# PCB_1_1.net
KiCad netlist of a schematic drawn in EAGLE
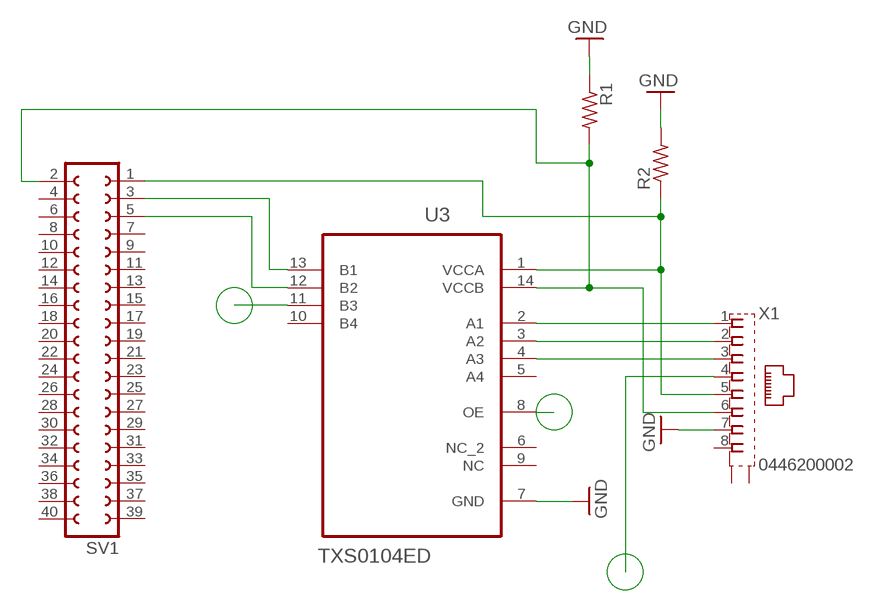
[diagram p0: schematic, sheet 1]

(export (version "E")
  (design (tool "Eeschema 10.0.6"))
  (components
    (comp (ref "R1")
      (value "R-US_R0805")
      (footprint "eagle-import:R0805")
      (libsource (lib "eagle-import") (part "R-US_R0805"))
    )
    (comp (ref "R2")
      (value "R-US_R0805")
      (footprint "eagle-import:R0805")
      (libsource (lib "eagle-import") (part "R-US_R0805"))
    )
    (comp (ref "SV1")
      (value "FE20-2")
      (footprint "eagle-import:FE20-2")
      (libsource (lib "eagle-import") (part "FE20-2"))
    )
    (comp (ref "U3")
      (value "TXS0104ED")
      (footprint "eagle-import:SOIC127P600X175-14N")
      (fields (field (name "MF") "Texas Instruments"))
      (libsource (lib "eagle-import") (part "TXS0104ED"))
    )
    (comp (ref "X1")
      (value "0446200002")
      (footprint "eagle-import:0446200002")
      (fields (field (name "MF") "Molex, LLC"))
      (libsource (lib "eagle-import") (part "0446200002"))
    )
  )
  (nets
    (net (code "1") (name "GND") (class "Default")
      (node (ref "R1") (pin "1") (pinfunction "1_1") (pintype "passive"))
      (node (ref "R2") (pin "2") (pinfunction "2_2") (pintype "passive"))
      (node (ref "U3") (pin "7") (pinfunction "GND_7") (pintype "passive"))
      (node (ref "X1") (pin "7") (pinfunction "7_7") (pintype "passive"))
    )
    (net (code "2") (name "Net-(U3-A1)") (class "Default")
      (node (ref "U3") (pin "2") (pinfunction "A1_2") (pintype "input"))
      (node (ref "X1") (pin "1") (pinfunction "1_1") (pintype "passive"))
    )
    (net (code "3") (name "Net-(U3-A2)") (class "Default")
      (node (ref "U3") (pin "3") (pinfunction "A2_3") (pintype "input"))
      (node (ref "X1") (pin "2") (pinfunction "2_2") (pintype "passive"))
    )
    (net (code "4") (name "Net-(U3-A3)") (class "Default")
      (node (ref "U3") (pin "4") (pinfunction "A3_4") (pintype "input"))
      (node (ref "X1") (pin "3") (pinfunction "3_3") (pintype "passive"))
    )
    (net (code "5") (name "Net-(U3-B1)") (class "Default")
      (node (ref "SV1") (pin "3") (pinfunction "3_3") (pintype "passive"))
      (node (ref "U3") (pin "13") (pinfunction "B1_13") (pintype "output"))
    )
    (net (code "6") (name "Net-(U3-B2)") (class "Default")
      (node (ref "SV1") (pin "5") (pinfunction "5_5") (pintype "passive"))
      (node (ref "U3") (pin "12") (pinfunction "B2_12") (pintype "output"))
    )
    (net (code "7") (name "Net-(U3-VCCA)") (class "Default")
      (node (ref "R2") (pin "1") (pinfunction "1_1") (pintype "passive"))
      (node (ref "SV1") (pin "1") (pinfunction "1_1") (pintype "passive"))
      (node (ref "U3") (pin "1") (pinfunction "VCCA_1") (pintype "power_in"))
      (node (ref "X1") (pin "5") (pinfunction "5_5") (pintype "passive"))
    )
    (net (code "8") (name "Net-(U3-VCCB)") (class "Default")
      (node (ref "R1") (pin "2") (pinfunction "2_2") (pintype "passive"))
      (node (ref "SV1") (pin "2") (pinfunction "2_2") (pintype "passive"))
      (node (ref "U3") (pin "14") (pinfunction "VCCB_14") (pintype "power_in"))
      (node (ref "X1") (pin "6") (pinfunction "6_6") (pintype "passive"))
    )
    (net (code "9") (name "unconnected-(SV1-Pad4)") (class "Default")
      (node (ref "SV1") (pin "4") (pinfunction "4_4") (pintype "passive"))
    )
    (net (code "10") (name "unconnected-(SV1-Pad6)") (class "Default")
      (node (ref "SV1") (pin "6") (pinfunction "6_6") (pintype "passive"))
    )
    (net (code "11") (name "unconnected-(SV1-Pad7)") (class "Default")
      (node (ref "SV1") (pin "7") (pinfunction "7_7") (pintype "passive"))
    )
    (net (code "12") (name "unconnected-(SV1-Pad8)") (class "Default")
      (node (ref "SV1") (pin "8") (pinfunction "8_8") (pintype "passive"))
    )
    (net (code "13") (name "unconnected-(SV1-Pad9)") (class "Default")
      (node (ref "SV1") (pin "9") (pinfunction "9_9") (pintype "passive"))
    )
    (net (code "14") (name "unconnected-(SV1-Pad10)") (class "Default")
      (node (ref "SV1") (pin "10") (pinfunction "10_10") (pintype "passive"))
    )
    (net (code "15") (name "unconnected-(SV1-Pad11)") (class "Default")
      (node (ref "SV1") (pin "11") (pinfunction "11_11") (pintype "passive"))
    )
    (net (code "16") (name "unconnected-(SV1-Pad12)") (class "Default")
      (node (ref "SV1") (pin "12") (pinfunction "12_12") (pintype "passive"))
    )
    (net (code "17") (name "unconnected-(SV1-Pad13)") (class "Default")
      (node (ref "SV1") (pin "13") (pinfunction "13_13") (pintype "passive"))
    )
    (net (code "18") (name "unconnected-(SV1-Pad14)") (class "Default")
      (node (ref "SV1") (pin "14") (pinfunction "14_14") (pintype "passive"))
    )
    (net (code "19") (name "unconnected-(SV1-Pad15)") (class "Default")
      (node (ref "SV1") (pin "15") (pinfunction "15_15") (pintype "passive"))
    )
    (net (code "20") (name "unconnected-(SV1-Pad16)") (class "Default")
      (node (ref "SV1") (pin "16") (pinfunction "16_16") (pintype "passive"))
    )
    (net (code "21") (name "unconnected-(SV1-Pad17)") (class "Default")
      (node (ref "SV1") (pin "17") (pinfunction "17_17") (pintype "passive"))
    )
    (net (code "22") (name "unconnected-(SV1-Pad18)") (class "Default")
      (node (ref "SV1") (pin "18") (pinfunction "18_18") (pintype "passive"))
    )
    (net (code "23") (name "unconnected-(SV1-Pad19)") (class "Default")
      (node (ref "SV1") (pin "19") (pinfunction "19_19") (pintype "passive"))
    )
    (net (code "24") (name "unconnected-(SV1-Pad20)") (class "Default")
      (node (ref "SV1") (pin "20") (pinfunction "20_20") (pintype "passive"))
    )
    (net (code "25") (name "unconnected-(SV1-Pad21)") (class "Default")
      (node (ref "SV1") (pin "21") (pinfunction "21_21") (pintype "passive"))
    )
    (net (code "26") (name "unconnected-(SV1-Pad22)") (class "Default")
      (node (ref "SV1") (pin "22") (pinfunction "22_22") (pintype "passive"))
    )
    (net (code "27") (name "unconnected-(SV1-Pad23)") (class "Default")
      (node (ref "SV1") (pin "23") (pinfunction "23_23") (pintype "passive"))
    )
    (net (code "28") (name "unconnected-(SV1-Pad24)") (class "Default")
      (node (ref "SV1") (pin "24") (pinfunction "24_24") (pintype "passive"))
    )
    (net (code "29") (name "unconnected-(SV1-Pad25)") (class "Default")
      (node (ref "SV1") (pin "25") (pinfunction "25_25") (pintype "passive"))
    )
    (net (code "30") (name "unconnected-(SV1-Pad26)") (class "Default")
      (node (ref "SV1") (pin "26") (pinfunction "26_26") (pintype "passive"))
    )
    (net (code "31") (name "unconnected-(SV1-Pad27)") (class "Default")
      (node (ref "SV1") (pin "27") (pinfunction "27_27") (pintype "passive"))
    )
    (net (code "32") (name "unconnected-(SV1-Pad28)") (class "Default")
      (node (ref "SV1") (pin "28") (pinfunction "28_28") (pintype "passive"))
    )
    (net (code "33") (name "unconnected-(SV1-Pad29)") (class "Default")
      (node (ref "SV1") (pin "29") (pinfunction "29_29") (pintype "passive"))
    )
    (net (code "34") (name "unconnected-(SV1-Pad30)") (class "Default")
      (node (ref "SV1") (pin "30") (pinfunction "30_30") (pintype "passive"))
    )
    (net (code "35") (name "unconnected-(SV1-Pad31)") (class "Default")
      (node (ref "SV1") (pin "31") (pinfunction "31_31") (pintype "passive"))
    )
    (net (code "36") (name "unconnected-(SV1-Pad32)") (class "Default")
      (node (ref "SV1") (pin "32") (pinfunction "32_32") (pintype "passive"))
    )
    (net (code "37") (name "unconnected-(SV1-Pad33)") (class "Default")
      (node (ref "SV1") (pin "33") (pinfunction "33_33") (pintype "passive"))
    )
    (net (code "38") (name "unconnected-(SV1-Pad34)") (class "Default")
      (node (ref "SV1") (pin "34") (pinfunction "34_34") (pintype "passive"))
    )
    (net (code "39") (name "unconnected-(SV1-Pad35)") (class "Default")
      (node (ref "SV1") (pin "35") (pinfunction "35_35") (pintype "passive"))
    )
    (net (code "40") (name "unconnected-(SV1-Pad36)") (class "Default")
      (node (ref "SV1") (pin "36") (pinfunction "36_36") (pintype "passive"))
    )
    (net (code "41") (name "unconnected-(SV1-Pad37)") (class "Default")
      (node (ref "SV1") (pin "37") (pinfunction "37_37") (pintype "passive"))
    )
    (net (code "42") (name "unconnected-(SV1-Pad38)") (class "Default")
      (node (ref "SV1") (pin "38") (pinfunction "38_38") (pintype "passive"))
    )
    (net (code "43") (name "unconnected-(SV1-Pad39)") (class "Default")
      (node (ref "SV1") (pin "39") (pinfunction "39_39") (pintype "passive"))
    )
    (net (code "44") (name "unconnected-(SV1-Pad40)") (class "Default")
      (node (ref "SV1") (pin "40") (pinfunction "40_40") (pintype "passive"))
    )
    (net (code "45") (name "unconnected-(U3-A4-Pad5)") (class "Default")
      (node (ref "U3") (pin "5") (pinfunction "A4_5") (pintype "input"))
    )
    (net (code "46") (name "unconnected-(U3-B3-Pad11)") (class "Default")
      (node (ref "U3") (pin "11") (pinfunction "B3_11") (pintype "output"))
    )
    (net (code "47") (name "unconnected-(U3-B4-Pad10)") (class "Default")
      (node (ref "U3") (pin "10") (pinfunction "B4_10") (pintype "output"))
    )
    (net (code "48") (name "unconnected-(U3-NC-Pad9)") (class "Default")
      (node (ref "U3") (pin "9") (pinfunction "NC_9") (pintype "no_connect"))
    )
    (net (code "49") (name "unconnected-(U3-NC_2-Pad6)") (class "Default")
      (node (ref "U3") (pin "6") (pinfunction "NC_2_6") (pintype "no_connect"))
    )
    (net (code "50") (name "unconnected-(U3-OE-Pad8)") (class "Default")
      (node (ref "U3") (pin "8") (pinfunction "OE_8") (pintype "input"))
    )
    (net (code "51") (name "unconnected-(X1-Pad4)") (class "Default")
      (node (ref "X1") (pin "4") (pinfunction "4_4") (pintype "passive"))
    )
    (net (code "52") (name "unconnected-(X1-Pad8)") (class "Default")
      (node (ref "X1") (pin "8") (pinfunction "8_8") (pintype "passive"))
    )
    (net (code "53") (name "unconnected-(X1-S1-PadS@1)") (class "Default")
      (node (ref "X1") (pin "S@1") (pinfunction "S1_S@1") (pintype "passive"))
    )
    (net (code "54") (name "unconnected-(X1-S2-PadS@2)") (class "Default")
      (node (ref "X1") (pin "S@2") (pinfunction "S2_S@2") (pintype "passive"))
    )
  )
)
